# FPGA_GTX.net
KiCad netlist of a schematic drawn in Altium Designer
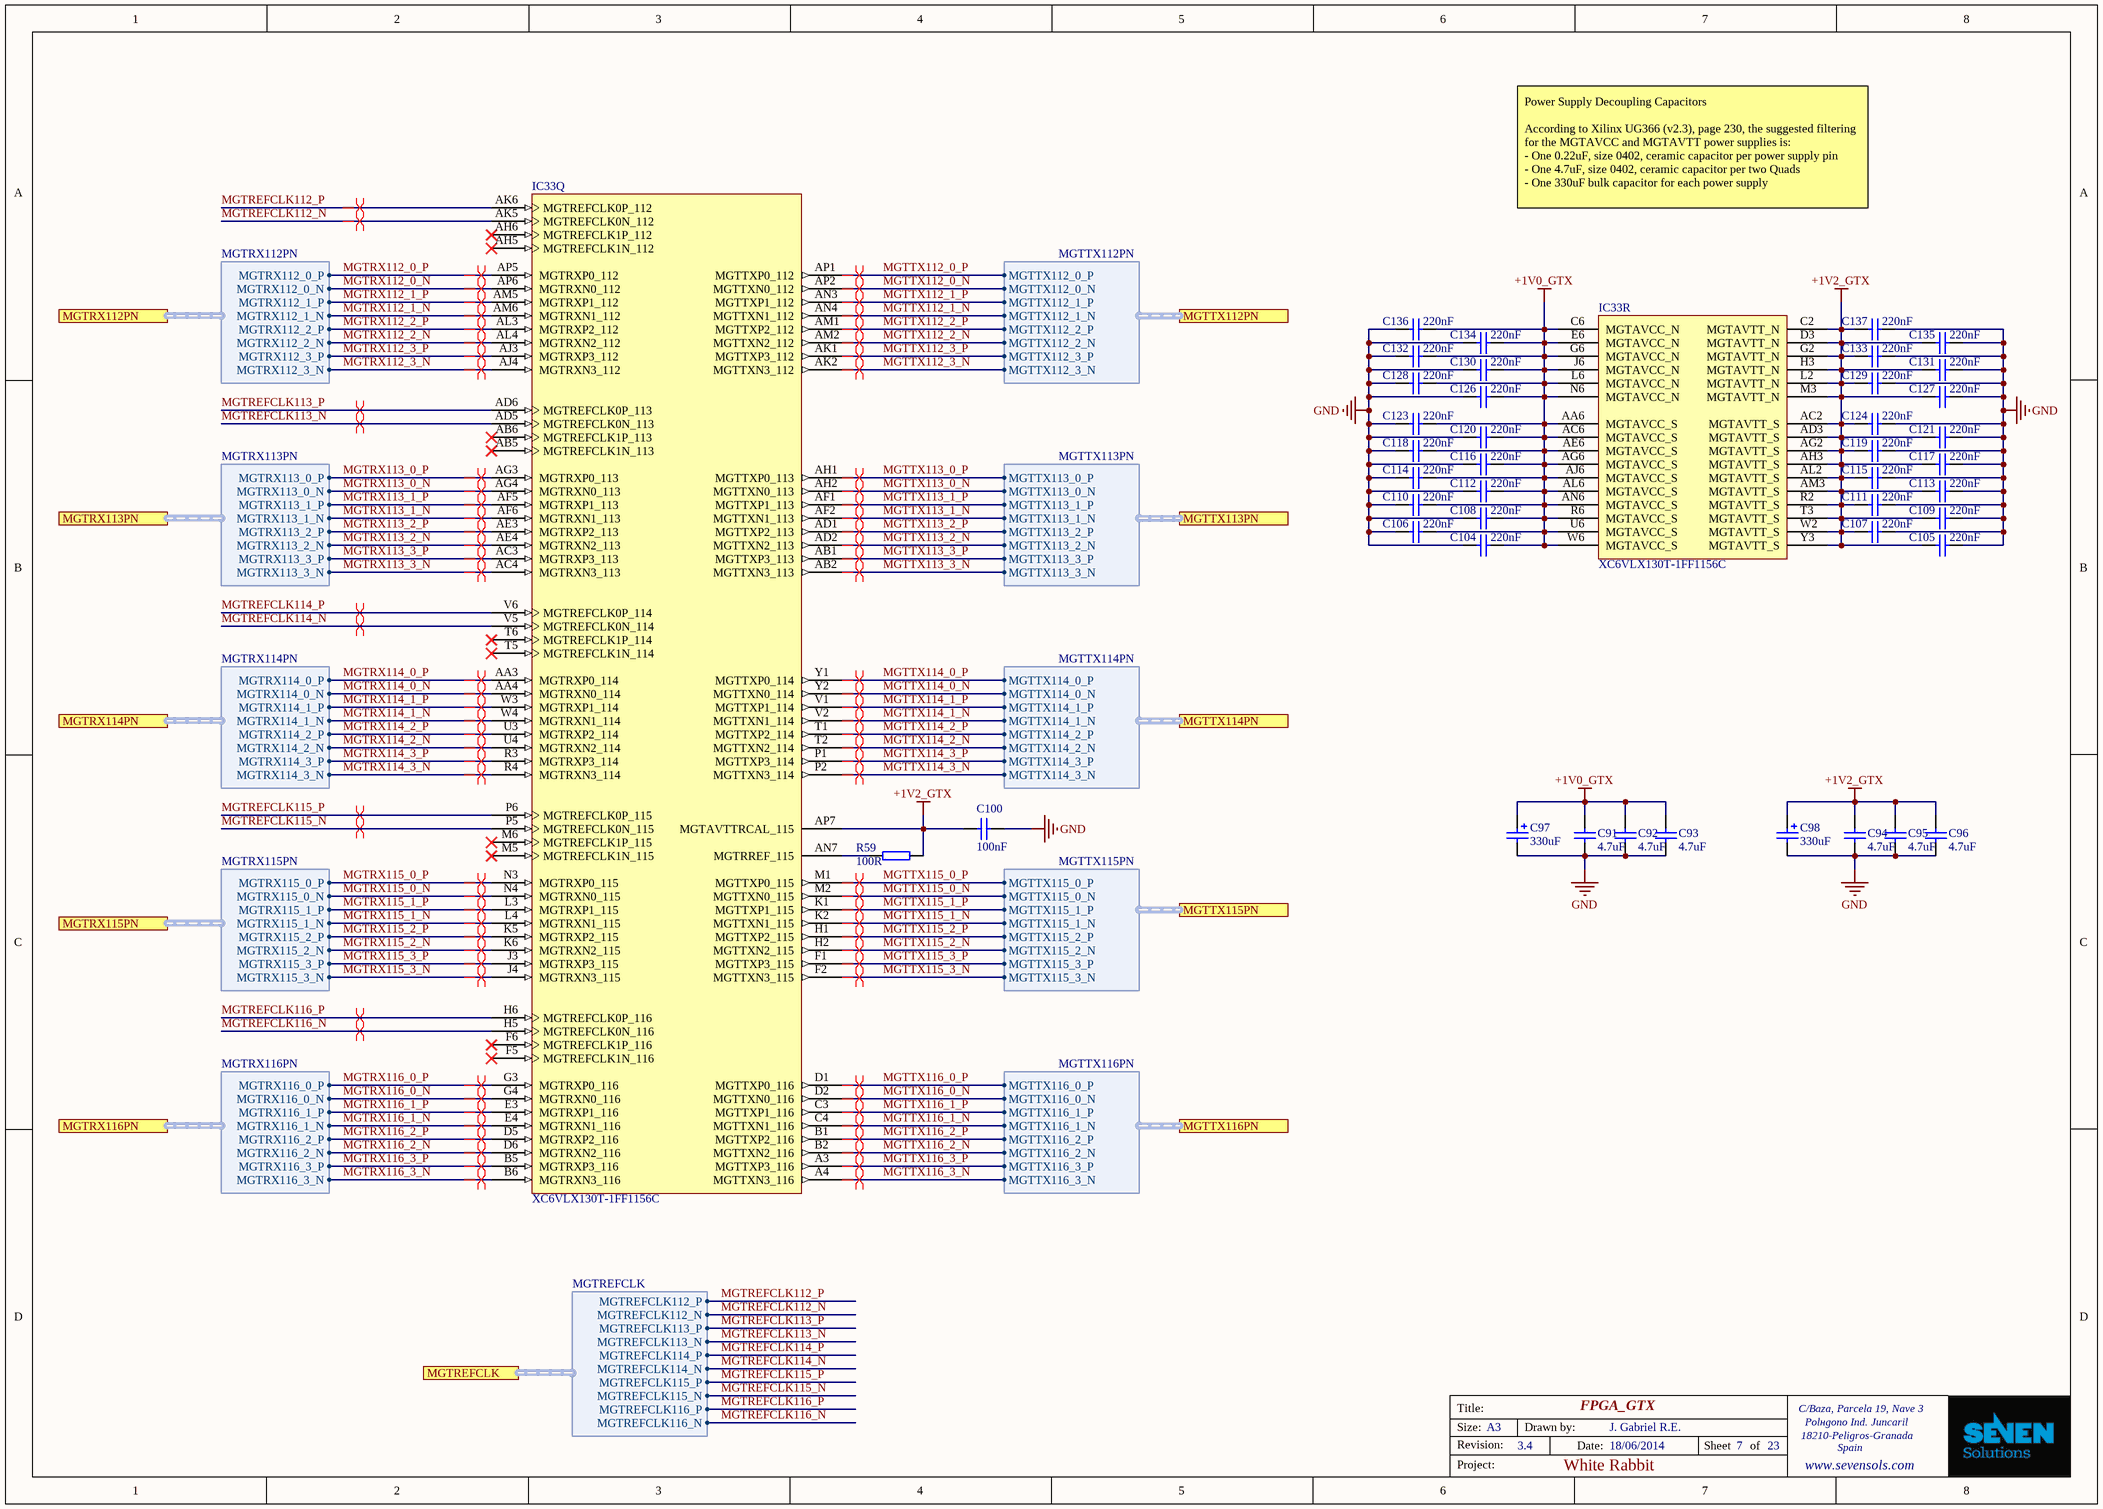
[diagram p0: FPGA_GTX.SchDoc]

(export (version "E")
  (design (tool "Eeschema 10.0.6"))
  (components
    (comp (ref "C91")
      (value "4.7uF")
      (footprint "CC1608-0603")
      (description "Capacitor")
      (fields
        (field (name "TOLERANCE") "±10%")
        (field (name "VOLTAGE") "10V")
        (field (name "PUBLISHER") "Altium Limited")
      )
      (libsource (lib "wr_switch") (part "Cap"))
    )
    (comp (ref "C92")
      (value "4.7uF")
      (footprint "CC1608-0603")
      (description "Capacitor")
      (fields
        (field (name "TOLERANCE") "±10%")
        (field (name "VOLTAGE") "10V")
        (field (name "PUBLISHER") "Altium Limited")
      )
      (libsource (lib "wr_switch") (part "Cap"))
    )
    (comp (ref "C93")
      (value "4.7uF")
      (footprint "CC1608-0603")
      (description "Capacitor")
      (fields
        (field (name "TOLERANCE") "±10%")
        (field (name "VOLTAGE") "10V")
        (field (name "PUBLISHER") "Altium Limited")
      )
      (libsource (lib "wr_switch") (part "Cap"))
    )
    (comp (ref "C94")
      (value "4.7uF")
      (footprint "CC1608-0603")
      (description "Capacitor")
      (fields
        (field (name "TOLERANCE") "±10%")
        (field (name "VOLTAGE") "10V")
        (field (name "PUBLISHER") "Altium Limited")
      )
      (libsource (lib "wr_switch") (part "Cap"))
    )
    (comp (ref "C95")
      (value "4.7uF")
      (footprint "CC1608-0603")
      (description "Capacitor")
      (fields
        (field (name "TOLERANCE") "±10%")
        (field (name "VOLTAGE") "10V")
        (field (name "PUBLISHER") "Altium Limited")
      )
      (libsource (lib "wr_switch") (part "Cap"))
    )
    (comp (ref "C96")
      (value "4.7uF")
      (footprint "CC1608-0603")
      (description "Capacitor")
      (fields
        (field (name "TOLERANCE") "±10%")
        (field (name "VOLTAGE") "10V")
        (field (name "PUBLISHER") "Altium Limited")
      )
      (libsource (lib "wr_switch") (part "Cap"))
    )
    (comp (ref "C97")
      (value "330uF")
      (footprint "D")
      (description "Polarized Capacitor Tantalum")
      (fields
        (field (name "TOLERANCE") "±20%")
        (field (name "VOLTAGE") "6.3V")
        (field (name "PUBLISHER") "Altium Limited")
      )
      (libsource (lib "wr_switch") (part "Cap Pol1"))
    )
    (comp (ref "C98")
      (value "330uF")
      (footprint "D")
      (description "Polarized Capacitor Tantalum")
      (fields
        (field (name "TOLERANCE") "±20%")
        (field (name "VOLTAGE") "6.3V")
        (field (name "PUBLISHER") "Altium Limited")
      )
      (libsource (lib "wr_switch") (part "Cap Pol1"))
    )
    (comp (ref "C100")
      (value "100nF")
      (footprint "CC1005-0402")
      (description "Capacitor")
      (fields
        (field (name "TOLERANCE") "±10%")
        (field (name "VOLTAGE") "16V")
        (field (name "PUBLISHER") "Altium Limited")
      )
      (libsource (lib "wr_switch") (part "Cap"))
    )
    (comp (ref "C104")
      (value "220nF")
      (footprint "CC1005-0402")
      (description "Capacitor")
      (fields
        (field (name "TOLERANCE") "±10%")
        (field (name "VOLTAGE") "16V")
        (field (name "PUBLISHER") "Altium Limited")
      )
      (libsource (lib "wr_switch") (part "Cap"))
    )
    (comp (ref "C105")
      (value "220nF")
      (footprint "CC1005-0402")
      (description "Capacitor")
      (fields
        (field (name "TOLERANCE") "±10%")
        (field (name "VOLTAGE") "16V")
        (field (name "PUBLISHER") "Altium Limited")
      )
      (libsource (lib "wr_switch") (part "Cap"))
    )
    (comp (ref "C106")
      (value "220nF")
      (footprint "CC1005-0402")
      (description "Capacitor")
      (fields
        (field (name "TOLERANCE") "±10%")
        (field (name "VOLTAGE") "16V")
        (field (name "PUBLISHER") "Altium Limited")
      )
      (libsource (lib "wr_switch") (part "Cap"))
    )
    (comp (ref "C107")
      (value "220nF")
      (footprint "CC1005-0402")
      (description "Capacitor")
      (fields
        (field (name "TOLERANCE") "±10%")
        (field (name "VOLTAGE") "16V")
        (field (name "PUBLISHER") "Altium Limited")
      )
      (libsource (lib "wr_switch") (part "Cap"))
    )
    (comp (ref "C108")
      (value "220nF")
      (footprint "CC1005-0402")
      (description "Capacitor")
      (fields
        (field (name "TOLERANCE") "±10%")
        (field (name "VOLTAGE") "16V")
        (field (name "PUBLISHER") "Altium Limited")
      )
      (libsource (lib "wr_switch") (part "Cap"))
    )
    (comp (ref "C109")
      (value "220nF")
      (footprint "CC1005-0402")
      (description "Capacitor")
      (fields
        (field (name "TOLERANCE") "±10%")
        (field (name "VOLTAGE") "16V")
        (field (name "PUBLISHER") "Altium Limited")
      )
      (libsource (lib "wr_switch") (part "Cap"))
    )
    (comp (ref "C110")
      (value "220nF")
      (footprint "CC1005-0402")
      (description "Capacitor")
      (fields
        (field (name "TOLERANCE") "±10%")
        (field (name "VOLTAGE") "16V")
        (field (name "PUBLISHER") "Altium Limited")
      )
      (libsource (lib "wr_switch") (part "Cap"))
    )
    (comp (ref "C111")
      (value "220nF")
      (footprint "CC1005-0402")
      (description "Capacitor")
      (fields
        (field (name "TOLERANCE") "±10%")
        (field (name "VOLTAGE") "16V")
        (field (name "PUBLISHER") "Altium Limited")
      )
      (libsource (lib "wr_switch") (part "Cap"))
    )
    (comp (ref "C112")
      (value "220nF")
      (footprint "CC1005-0402")
      (description "Capacitor")
      (fields
        (field (name "TOLERANCE") "±10%")
        (field (name "VOLTAGE") "16V")
        (field (name "PUBLISHER") "Altium Limited")
      )
      (libsource (lib "wr_switch") (part "Cap"))
    )
    (comp (ref "C113")
      (value "220nF")
      (footprint "CC1005-0402")
      (description "Capacitor")
      (fields
        (field (name "TOLERANCE") "±10%")
        (field (name "VOLTAGE") "16V")
        (field (name "PUBLISHER") "Altium Limited")
      )
      (libsource (lib "wr_switch") (part "Cap"))
    )
    (comp (ref "C114")
      (value "220nF")
      (footprint "CC1005-0402")
      (description "Capacitor")
      (fields
        (field (name "TOLERANCE") "±10%")
        (field (name "VOLTAGE") "16V")
        (field (name "PUBLISHER") "Altium Limited")
      )
      (libsource (lib "wr_switch") (part "Cap"))
    )
    (comp (ref "C115")
      (value "220nF")
      (footprint "CC1005-0402")
      (description "Capacitor")
      (fields
        (field (name "TOLERANCE") "±10%")
        (field (name "VOLTAGE") "16V")
        (field (name "PUBLISHER") "Altium Limited")
      )
      (libsource (lib "wr_switch") (part "Cap"))
    )
    (comp (ref "C116")
      (value "220nF")
      (footprint "CC1005-0402")
      (description "Capacitor")
      (fields
        (field (name "TOLERANCE") "±10%")
        (field (name "VOLTAGE") "16V")
        (field (name "PUBLISHER") "Altium Limited")
      )
      (libsource (lib "wr_switch") (part "Cap"))
    )
    (comp (ref "C117")
      (value "220nF")
      (footprint "CC1005-0402")
      (description "Capacitor")
      (fields
        (field (name "TOLERANCE") "±10%")
        (field (name "VOLTAGE") "16V")
        (field (name "PUBLISHER") "Altium Limited")
      )
      (libsource (lib "wr_switch") (part "Cap"))
    )
    (comp (ref "C118")
      (value "220nF")
      (footprint "CC1005-0402")
      (description "Capacitor")
      (fields
        (field (name "TOLERANCE") "±10%")
        (field (name "VOLTAGE") "16V")
        (field (name "PUBLISHER") "Altium Limited")
      )
      (libsource (lib "wr_switch") (part "Cap"))
    )
    (comp (ref "C119")
      (value "220nF")
      (footprint "CC1005-0402")
      (description "Capacitor")
      (fields
        (field (name "TOLERANCE") "±10%")
        (field (name "VOLTAGE") "16V")
        (field (name "PUBLISHER") "Altium Limited")
      )
      (libsource (lib "wr_switch") (part "Cap"))
    )
    (comp (ref "C120")
      (value "220nF")
      (footprint "CC1005-0402")
      (description "Capacitor")
      (fields
        (field (name "TOLERANCE") "±10%")
        (field (name "VOLTAGE") "16V")
        (field (name "PUBLISHER") "Altium Limited")
      )
      (libsource (lib "wr_switch") (part "Cap"))
    )
    (comp (ref "C121")
      (value "220nF")
      (footprint "CC1005-0402")
      (description "Capacitor")
      (fields
        (field (name "TOLERANCE") "±10%")
        (field (name "VOLTAGE") "16V")
        (field (name "PUBLISHER") "Altium Limited")
      )
      (libsource (lib "wr_switch") (part "Cap"))
    )
    (comp (ref "C123")
      (value "220nF")
      (footprint "CC1005-0402")
      (description "Capacitor")
      (fields
        (field (name "TOLERANCE") "±10%")
        (field (name "VOLTAGE") "16V")
        (field (name "PUBLISHER") "Altium Limited")
      )
      (libsource (lib "wr_switch") (part "Cap"))
    )
    (comp (ref "C124")
      (value "220nF")
      (footprint "CC1005-0402")
      (description "Capacitor")
      (fields
        (field (name "TOLERANCE") "±10%")
        (field (name "VOLTAGE") "16V")
        (field (name "PUBLISHER") "Altium Limited")
      )
      (libsource (lib "wr_switch") (part "Cap"))
    )
    (comp (ref "C126")
      (value "220nF")
      (footprint "CC1005-0402")
      (description "Capacitor")
      (fields
        (field (name "TOLERANCE") "±10%")
        (field (name "VOLTAGE") "16V")
        (field (name "PUBLISHER") "Altium Limited")
      )
      (libsource (lib "wr_switch") (part "Cap"))
    )
    (comp (ref "C127")
      (value "220nF")
      (footprint "CC1005-0402")
      (description "Capacitor")
      (fields
        (field (name "TOLERANCE") "±10%")
        (field (name "VOLTAGE") "16V")
        (field (name "PUBLISHER") "Altium Limited")
      )
      (libsource (lib "wr_switch") (part "Cap"))
    )
    (comp (ref "C128")
      (value "220nF")
      (footprint "CC1005-0402")
      (description "Capacitor")
      (fields
        (field (name "TOLERANCE") "±10%")
        (field (name "VOLTAGE") "16V")
        (field (name "PUBLISHER") "Altium Limited")
      )
      (libsource (lib "wr_switch") (part "Cap"))
    )
    (comp (ref "C129")
      (value "220nF")
      (footprint "CC1005-0402")
      (description "Capacitor")
      (fields
        (field (name "TOLERANCE") "±10%")
        (field (name "VOLTAGE") "16V")
        (field (name "PUBLISHER") "Altium Limited")
      )
      (libsource (lib "wr_switch") (part "Cap"))
    )
    (comp (ref "C130")
      (value "220nF")
      (footprint "CC1005-0402")
      (description "Capacitor")
      (fields
        (field (name "TOLERANCE") "±10%")
        (field (name "VOLTAGE") "16V")
        (field (name "PUBLISHER") "Altium Limited")
      )
      (libsource (lib "wr_switch") (part "Cap"))
    )
    (comp (ref "C131")
      (value "220nF")
      (footprint "CC1005-0402")
      (description "Capacitor")
      (fields
        (field (name "TOLERANCE") "±10%")
        (field (name "VOLTAGE") "16V")
        (field (name "PUBLISHER") "Altium Limited")
      )
      (libsource (lib "wr_switch") (part "Cap"))
    )
    (comp (ref "C132")
      (value "220nF")
      (footprint "CC1005-0402")
      (description "Capacitor")
      (fields
        (field (name "TOLERANCE") "±10%")
        (field (name "VOLTAGE") "16V")
        (field (name "PUBLISHER") "Altium Limited")
      )
      (libsource (lib "wr_switch") (part "Cap"))
    )
    (comp (ref "C133")
      (value "220nF")
      (footprint "CC1005-0402")
      (description "Capacitor")
      (fields
        (field (name "TOLERANCE") "±10%")
        (field (name "VOLTAGE") "16V")
        (field (name "PUBLISHER") "Altium Limited")
      )
      (libsource (lib "wr_switch") (part "Cap"))
    )
    (comp (ref "C134")
      (value "220nF")
      (footprint "CC1005-0402")
      (description "Capacitor")
      (fields
        (field (name "TOLERANCE") "±10%")
        (field (name "VOLTAGE") "16V")
        (field (name "PUBLISHER") "Altium Limited")
      )
      (libsource (lib "wr_switch") (part "Cap"))
    )
    (comp (ref "C135")
      (value "220nF")
      (footprint "CC1005-0402")
      (description "Capacitor")
      (fields
        (field (name "TOLERANCE") "±10%")
        (field (name "VOLTAGE") "16V")
        (field (name "PUBLISHER") "Altium Limited")
      )
      (libsource (lib "wr_switch") (part "Cap"))
    )
    (comp (ref "C136")
      (value "220nF")
      (footprint "CC1005-0402")
      (description "Capacitor")
      (fields
        (field (name "TOLERANCE") "±10%")
        (field (name "VOLTAGE") "16V")
        (field (name "PUBLISHER") "Altium Limited")
      )
      (libsource (lib "wr_switch") (part "Cap"))
    )
    (comp (ref "C137")
      (value "220nF")
      (footprint "CC1005-0402")
      (description "Capacitor")
      (fields
        (field (name "TOLERANCE") "±10%")
        (field (name "VOLTAGE") "16V")
        (field (name "PUBLISHER") "Altium Limited")
      )
      (libsource (lib "wr_switch") (part "Cap"))
    )
    (comp (ref "IC33")
      (value "XC6VLX130T-1FF1156C")
      (footprint "FF1156")
      (fields (field (name "PUBLISHER") "Altium Limited"))
      (libsource (lib "Xilinx Virtex-6") (part "XC6VLX130T-1FF1156C"))
    )
    (comp (ref "R59")
      (value "100R")
      (footprint "0402")
      (description "SMD Resistor")
      (fields (field (name "TOLERANCE") "±1%"))
      (libsource (lib "wr_switch") (part "RES_SMD"))
    )
  )
  (nets
    (net (code "12") (name "+1V0_GTX") (class "Default")
      (node (ref "C104") (pin "2") (pinfunction "2_2") (pintype "passive"))
      (node (ref "C106") (pin "2") (pinfunction "2_2") (pintype "passive"))
      (node (ref "C108") (pin "2") (pinfunction "2_2") (pintype "passive"))
      (node (ref "C110") (pin "2") (pinfunction "2_2") (pintype "passive"))
      (node (ref "C112") (pin "2") (pinfunction "2_2") (pintype "passive"))
      (node (ref "C114") (pin "2") (pinfunction "2_2") (pintype "passive"))
      (node (ref "C116") (pin "2") (pinfunction "2_2") (pintype "passive"))
      (node (ref "C118") (pin "2") (pinfunction "2_2") (pintype "passive"))
      (node (ref "C120") (pin "2") (pinfunction "2_2") (pintype "passive"))
      (node (ref "C123") (pin "2") (pinfunction "2_2") (pintype "passive"))
      (node (ref "C126") (pin "2") (pinfunction "2_2") (pintype "passive"))
      (node (ref "C128") (pin "2") (pinfunction "2_2") (pintype "passive"))
      (node (ref "C130") (pin "2") (pinfunction "2_2") (pintype "passive"))
      (node (ref "C132") (pin "2") (pinfunction "2_2") (pintype "passive"))
      (node (ref "C134") (pin "2") (pinfunction "2_2") (pintype "passive"))
      (node (ref "C136") (pin "2") (pinfunction "2_2") (pintype "passive"))
      (node (ref "C91") (pin "2") (pinfunction "2_2") (pintype "passive"))
      (node (ref "C92") (pin "2") (pinfunction "2_2") (pintype "passive"))
      (node (ref "C93") (pin "2") (pinfunction "2_2") (pintype "passive"))
      (node (ref "C97") (pin "1") (pinfunction "1_1") (pintype "passive"))
      (node (ref "IC33") (pin "AA6") (pinfunction "MGTAVCC_S_AA6") (pintype "power_in"))
      (node (ref "IC33") (pin "AC6") (pinfunction "MGTAVCC_S_AC6") (pintype "power_in"))
      (node (ref "IC33") (pin "AE6") (pinfunction "MGTAVCC_S_AE6") (pintype "power_in"))
      (node (ref "IC33") (pin "AG6") (pinfunction "MGTAVCC_S_AG6") (pintype "power_in"))
      (node (ref "IC33") (pin "AJ6") (pinfunction "MGTAVCC_S_AJ6") (pintype "power_in"))
      (node (ref "IC33") (pin "AL6") (pinfunction "MGTAVCC_S_AL6") (pintype "power_in"))
      (node (ref "IC33") (pin "AN6") (pinfunction "MGTAVCC_S_AN6") (pintype "power_in"))
      (node (ref "IC33") (pin "C6") (pinfunction "MGTAVCC_N_C6") (pintype "power_in"))
      (node (ref "IC33") (pin "E6") (pinfunction "MGTAVCC_N_E6") (pintype "power_in"))
      (node (ref "IC33") (pin "G6") (pinfunction "MGTAVCC_N_G6") (pintype "power_in"))
      (node (ref "IC33") (pin "J6") (pinfunction "MGTAVCC_N_J6") (pintype "power_in"))
      (node (ref "IC33") (pin "L6") (pinfunction "MGTAVCC_N_L6") (pintype "power_in"))
      (node (ref "IC33") (pin "N6") (pinfunction "MGTAVCC_N_N6") (pintype "power_in"))
      (node (ref "IC33") (pin "R6") (pinfunction "MGTAVCC_S_R6") (pintype "power_in"))
      (node (ref "IC33") (pin "U6") (pinfunction "MGTAVCC_S_U6") (pintype "power_in"))
      (node (ref "IC33") (pin "W6") (pinfunction "MGTAVCC_S_W6") (pintype "power_in"))
    )
    (net (code "13") (name "+1V2_GTX") (class "Default")
      (node (ref "C100") (pin "2") (pinfunction "2_2") (pintype "passive"))
      (node (ref "C105") (pin "1") (pinfunction "1_1") (pintype "passive"))
      (node (ref "C107") (pin "1") (pinfunction "1_1") (pintype "passive"))
      (node (ref "C109") (pin "1") (pinfunction "1_1") (pintype "passive"))
      (node (ref "C111") (pin "1") (pinfunction "1_1") (pintype "passive"))
      (node (ref "C113") (pin "1") (pinfunction "1_1") (pintype "passive"))
      (node (ref "C115") (pin "1") (pinfunction "1_1") (pintype "passive"))
      (node (ref "C117") (pin "1") (pinfunction "1_1") (pintype "passive"))
      (node (ref "C119") (pin "1") (pinfunction "1_1") (pintype "passive"))
      (node (ref "C121") (pin "1") (pinfunction "1_1") (pintype "passive"))
      (node (ref "C124") (pin "1") (pinfunction "1_1") (pintype "passive"))
      (node (ref "C127") (pin "1") (pinfunction "1_1") (pintype "passive"))
      (node (ref "C129") (pin "1") (pinfunction "1_1") (pintype "passive"))
      (node (ref "C131") (pin "1") (pinfunction "1_1") (pintype "passive"))
      (node (ref "C133") (pin "1") (pinfunction "1_1") (pintype "passive"))
      (node (ref "C135") (pin "1") (pinfunction "1_1") (pintype "passive"))
      (node (ref "C137") (pin "1") (pinfunction "1_1") (pintype "passive"))
      (node (ref "C94") (pin "2") (pinfunction "2_2") (pintype "passive"))
      (node (ref "C95") (pin "2") (pinfunction "2_2") (pintype "passive"))
      (node (ref "C96") (pin "2") (pinfunction "2_2") (pintype "passive"))
      (node (ref "C98") (pin "1") (pinfunction "1_1") (pintype "passive"))
      (node (ref "IC33") (pin "AC2") (pinfunction "MGTAVTT_S_AC2") (pintype "power_in"))
      (node (ref "IC33") (pin "AD3") (pinfunction "MGTAVTT_S_AD3") (pintype "power_in"))
      (node (ref "IC33") (pin "AG2") (pinfunction "MGTAVTT_S_AG2") (pintype "power_in"))
      (node (ref "IC33") (pin "AH3") (pinfunction "MGTAVTT_S_AH3") (pintype "power_in"))
      (node (ref "IC33") (pin "AL2") (pinfunction "MGTAVTT_S_AL2") (pintype "power_in"))
      (node (ref "IC33") (pin "AM3") (pinfunction "MGTAVTT_S_AM3") (pintype "power_in"))
      (node (ref "IC33") (pin "AP7") (pinfunction "MGTAVTTRCAL_115_AP7") (pintype "passive"))
      (node (ref "IC33") (pin "C2") (pinfunction "MGTAVTT_N_C2") (pintype "power_in"))
      (node (ref "IC33") (pin "D3") (pinfunction "MGTAVTT_N_D3") (pintype "power_in"))
      (node (ref "IC33") (pin "G2") (pinfunction "MGTAVTT_N_G2") (pintype "power_in"))
      (node (ref "IC33") (pin "H3") (pinfunction "MGTAVTT_N_H3") (pintype "power_in"))
      (node (ref "IC33") (pin "L2") (pinfunction "MGTAVTT_N_L2") (pintype "power_in"))
      (node (ref "IC33") (pin "M3") (pinfunction "MGTAVTT_N_M3") (pintype "power_in"))
      (node (ref "IC33") (pin "R2") (pinfunction "MGTAVTT_S_R2") (pintype "power_in"))
      (node (ref "IC33") (pin "T3") (pinfunction "MGTAVTT_S_T3") (pintype "power_in"))
      (node (ref "IC33") (pin "W2") (pinfunction "MGTAVTT_S_W2") (pintype "power_in"))
      (node (ref "IC33") (pin "Y3") (pinfunction "MGTAVTT_S_Y3") (pintype "power_in"))
      (node (ref "R59") (pin "1") (pinfunction "1_1") (pintype "passive"))
    )
    (net (code "14") (name "/MGTREFCLK112_N") (class "Default")
      (node (ref "IC33") (pin "AK5") (pinfunction "MGTREFCLK0N_112_AK5") (pintype "input"))
    )
    (net (code "15") (name "/MGTREFCLK112_P") (class "Default")
      (node (ref "IC33") (pin "AK6") (pinfunction "MGTREFCLK0P_112_AK6") (pintype "input"))
    )
    (net (code "16") (name "/MGTREFCLK113_N") (class "Default")
      (node (ref "IC33") (pin "AD5") (pinfunction "MGTREFCLK0N_113_AD5") (pintype "input"))
    )
    (net (code "17") (name "/MGTREFCLK113_P") (class "Default")
      (node (ref "IC33") (pin "AD6") (pinfunction "MGTREFCLK0P_113_AD6") (pintype "input"))
    )
    (net (code "18") (name "/MGTREFCLK114_N") (class "Default")
      (node (ref "IC33") (pin "V5") (pinfunction "MGTREFCLK0N_114_V5") (pintype "input"))
    )
    (net (code "19") (name "/MGTREFCLK114_P") (class "Default")
      (node (ref "IC33") (pin "V6") (pinfunction "MGTREFCLK0P_114_V6") (pintype "input"))
    )
    (net (code "20") (name "/MGTREFCLK115_N") (class "Default")
      (node (ref "IC33") (pin "P5") (pinfunction "MGTREFCLK0N_115_P5") (pintype "input"))
    )
    (net (code "21") (name "/MGTREFCLK115_P") (class "Default")
      (node (ref "IC33") (pin "P6") (pinfunction "MGTREFCLK0P_115_P6") (pintype "input"))
    )
    (net (code "22") (name "/MGTREFCLK116_N") (class "Default")
      (node (ref "IC33") (pin "H5") (pinfunction "MGTREFCLK0N_116_H5") (pintype "input"))
    )
    (net (code "23") (name "/MGTREFCLK116_P") (class "Default")
      (node (ref "IC33") (pin "H6") (pinfunction "MGTREFCLK0P_116_H6") (pintype "input"))
    )
    (net (code "24") (name "/MGTRX112_0_N") (class "Default")
      (node (ref "IC33") (pin "AP6") (pinfunction "MGTRXN0_112_AP6") (pintype "input"))
    )
    (net (code "25") (name "/MGTRX112_0_P") (class "Default")
      (node (ref "IC33") (pin "AP5") (pinfunction "MGTRXP0_112_AP5") (pintype "input"))
    )
    (net (code "26") (name "/MGTRX112_1_N") (class "Default")
      (node (ref "IC33") (pin "AM6") (pinfunction "MGTRXN1_112_AM6") (pintype "input"))
    )
    (net (code "27") (name "/MGTRX112_1_P") (class "Default")
      (node (ref "IC33") (pin "AM5") (pinfunction "MGTRXP1_112_AM5") (pintype "input"))
    )
    (net (code "28") (name "/MGTRX112_2_N") (class "Default")
      (node (ref "IC33") (pin "AL4") (pinfunction "MGTRXN2_112_AL4") (pintype "input"))
    )
    (net (code "29") (name "/MGTRX112_2_P") (class "Default")
      (node (ref "IC33") (pin "AL3") (pinfunction "MGTRXP2_112_AL3") (pintype "input"))
    )
    (net (code "30") (name "/MGTRX112_3_N") (class "Default")
      (node (ref "IC33") (pin "AJ4") (pinfunction "MGTRXN3_112_AJ4") (pintype "input"))
    )
    (net (code "31") (name "/MGTRX112_3_P") (class "Default")
      (node (ref "IC33") (pin "AJ3") (pinfunction "MGTRXP3_112_AJ3") (pintype "input"))
    )
    (net (code "32") (name "/MGTRX113_0_N") (class "Default")
      (node (ref "IC33") (pin "AG4") (pinfunction "MGTRXN0_113_AG4") (pintype "input"))
    )
    (net (code "33") (name "/MGTRX113_0_P") (class "Default")
      (node (ref "IC33") (pin "AG3") (pinfunction "MGTRXP0_113_AG3") (pintype "input"))
    )
    (net (code "34") (name "/MGTRX113_1_N") (class "Default")
      (node (ref "IC33") (pin "AF6") (pinfunction "MGTRXN1_113_AF6") (pintype "input"))
    )
    (net (code "35") (name "/MGTRX113_1_P") (class "Default")
      (node (ref "IC33") (pin "AF5") (pinfunction "MGTRXP1_113_AF5") (pintype "input"))
    )
    (net (code "36") (name "/MGTRX113_2_N") (class "Default")
      (node (ref "IC33") (pin "AE4") (pinfunction "MGTRXN2_113_AE4") (pintype "input"))
    )
    (net (code "37") (name "/MGTRX113_2_P") (class "Default")
      (node (ref "IC33") (pin "AE3") (pinfunction "MGTRXP2_113_AE3") (pintype "input"))
    )
    (net (code "38") (name "/MGTRX113_3_N") (class "Default")
      (node (ref "IC33") (pin "AC4") (pinfunction "MGTRXN3_113_AC4") (pintype "input"))
    )
    (net (code "39") (name "/MGTRX113_3_P") (class "Default")
      (node (ref "IC33") (pin "AC3") (pinfunction "MGTRXP3_113_AC3") (pintype "input"))
    )
    (net (code "40") (name "/MGTRX114_0_N") (class "Default")
      (node (ref "IC33") (pin "AA4") (pinfunction "MGTRXN0_114_AA4") (pintype "input"))
    )
    (net (code "41") (name "/MGTRX114_0_P") (class "Default")
      (node (ref "IC33") (pin "AA3") (pinfunction "MGTRXP0_114_AA3") (pintype "input"))
    )
    (net (code "42") (name "/MGTRX114_1_N") (class "Default")
      (node (ref "IC33") (pin "W4") (pinfunction "MGTRXN1_114_W4") (pintype "input"))
    )
    (net (code "43") (name "/MGTRX114_1_P") (class "Default")
      (node (ref "IC33") (pin "W3") (pinfunction "MGTRXP1_114_W3") (pintype "input"))
    )
    (net (code "44") (name "/MGTRX114_2_N") (class "Default")
      (node (ref "IC33") (pin "U4") (pinfunction "MGTRXN2_114_U4") (pintype "input"))
    )
    (net (code "45") (name "/MGTRX114_2_P") (class "Default")
      (node (ref "IC33") (pin "U3") (pinfunction "MGTRXP2_114_U3") (pintype "input"))
    )
    (net (code "46") (name "/MGTRX114_3_N") (class "Default")
      (node (ref "IC33") (pin "R4") (pinfunction "MGTRXN3_114_R4") (pintype "input"))
    )
    (net (code "47") (name "/MGTRX114_3_P") (class "Default")
      (node (ref "IC33") (pin "R3") (pinfunction "MGTRXP3_114_R3") (pintype "input"))
    )
    (net (code "48") (name "/MGTRX115_0_N") (class "Default")
      (node (ref "IC33") (pin "N4") (pinfunction "MGTRXN0_115_N4") (pintype "input"))
    )
    (net (code "49") (name "/MGTRX115_0_P") (class "Default")
      (node (ref "IC33") (pin "N3") (pinfunction "MGTRXP0_115_N3") (pintype "input"))
    )
    (net (code "50") (name "/MGTRX115_1_N") (class "Default")
      (node (ref "IC33") (pin "L4") (pinfunction "MGTRXN1_115_L4") (pintype "input"))
    )
    (net (code "51") (name "/MGTRX115_1_P") (class "Default")
      (node (ref "IC33") (pin "L3") (pinfunction "MGTRXP1_115_L3") (pintype "input"))
    )
    (net (code "52") (name "/MGTRX115_2_N") (class "Default")
      (node (ref "IC33") (pin "K6") (pinfunction "MGTRXN2_115_K6") (pintype "input"))
    )
    (net (code "53") (name "/MGTRX115_2_P") (class "Default")
      (node (ref "IC33") (pin "K5") (pinfunction "MGTRXP2_115_K5") (pintype "input"))
    )
    (net (code "54") (name "/MGTRX115_3_N") (class "Default")
      (node (ref "IC33") (pin "J4") (pinfunction "MGTRXN3_115_J4") (pintype "input"))
    )
    (net (code "55") (name "/MGTRX115_3_P") (class "Default")
      (node (ref "IC33") (pin "J3") (pinfunction "MGTRXP3_115_J3") (pintype "input"))
    )
    (net (code "56") (name "/MGTRX116_0_N") (class "Default")
      (node (ref "IC33") (pin "G4") (pinfunction "MGTRXN0_116_G4") (pintype "input"))
    )
    (net (code "57") (name "/MGTRX116_0_P") (class "Default")
      (node (ref "IC33") (pin "G3") (pinfunction "MGTRXP0_116_G3") (pintype "input"))
    )
    (net (code "58") (name "/MGTRX116_1_N") (class "Default")
      (node (ref "IC33") (pin "E4") (pinfunction "MGTRXN1_116_E4") (pintype "input"))
    )
    (net (code "59") (name "/MGTRX116_1_P") (class "Default")
      (node (ref "IC33") (pin "E3") (pinfunction "MGTRXP1_116_E3") (pintype "input"))
    )
    (net (code "60") (name "/MGTRX116_2_N") (class "Default")
      (node (ref "IC33") (pin "D6") (pinfunction "MGTRXN2_116_D6") (pintype "input"))
    )
    (net (code "61") (name "/MGTRX116_2_P") (class "Default")
      (node (ref "IC33") (pin "D5") (pinfunction "MGTRXP2_116_D5") (pintype "input"))
    )
    (net (code "62") (name "/MGTRX116_3_N") (class "Default")
      (node (ref "IC33") (pin "B6") (pinfunction "MGTRXN3_116_B6") (pintype "input"))
    )
    (net (code "63") (name "/MGTRX116_3_P") (class "Default")
      (node (ref "IC33") (pin "B5") (pinfunction "MGTRXP3_116_B5") (pintype "input"))
    )
    (net (code "64") (name "/MGTTX112_0_N") (class "Default")
      (node (ref "IC33") (pin "AP2") (pinfunction "MGTTXN0_112_AP2") (pintype "output"))
    )
    (net (code "65") (name "/MGTTX112_0_P") (class "Default")
      (node (ref "IC33") (pin "AP1") (pinfunction "MGTTXP0_112_AP1") (pintype "output"))
    )
    (net (code "66") (name "/MGTTX112_1_N") (class "Default")
      (node (ref "IC33") (pin "AN4") (pinfunction "MGTTXN1_112_AN4") (pintype "output"))
    )
    (net (code "67") (name "/MGTTX112_1_P") (class "Default")
      (node (ref "IC33") (pin "AN3") (pinfunction "MGTTXP1_112_AN3") (pintype "output"))
    )
    (net (code "68") (name "/MGTTX112_2_N") (class "Default")
      (node (ref "IC33") (pin "AM2") (pinfunction "MGTTXN2_112_AM2") (pintype "output"))
    )
    (net (code "69") (name "/MGTTX112_2_P") (class "Default")
      (node (ref "IC33") (pin "AM1") (pinfunction "MGTTXP2_112_AM1") (pintype "output"))
    )
    (net (code "70") (name "/MGTTX112_3_N") (class "Default")
      (node (ref "IC33") (pin "AK2") (pinfunction "MGTTXN3_112_AK2") (pintype "output"))
    )
    (net (code "71") (name "/MGTTX112_3_P") (class "Default")
      (node (ref "IC33") (pin "AK1") (pinfunction "MGTTXP3_112_AK1") (pintype "output"))
    )
    (net (code "72") (name "/MGTTX113_0_N") (class "Default")
      (node (ref "IC33") (pin "AH2") (pinfunction "MGTTXN0_113_AH2") (pintype "output"))
    )
    (net (code "73") (name "/MGTTX113_0_P") (class "Default")
      (node (ref "IC33") (pin "AH1") (pinfunction "MGTTXP0_113_AH1") (pintype "output"))
    )
    (net (code "74") (name "/MGTTX113_1_N") (class "Default")
      (node (ref "IC33") (pin "AF2") (pinfunction "MGTTXN1_113_AF2") (pintype "output"))
    )
    (net (code "75") (name "/MGTTX113_1_P") (class "Default")
      (node (ref "IC33") (pin "AF1") (pinfunction "MGTTXP1_113_AF1") (pintype "output"))
    )
    (net (code "76") (name "/MGTTX113_2_N") (class "Default")
      (node (ref "IC33") (pin "AD2") (pinfunction "MGTTXN2_113_AD2") (pintype "output"))
    )
    (net (code "77") (name "/MGTTX113_2_P") (class "Default")
      (node (ref "IC33") (pin "AD1") (pinfunction "MGTTXP2_113_AD1") (pintype "output"))
    )
    (net (code "78") (name "/MGTTX113_3_N") (class "Default")
      (node (ref "IC33") (pin "AB2") (pinfunction "MGTTXN3_113_AB2") (pintype "output"))
    )
    (net (code "79") (name "/MGTTX113_3_P") (class "Default")
      (node (ref "IC33") (pin "AB1") (pinfunction "MGTTXP3_113_AB1") (pintype "output"))
    )
    (net (code "80") (name "/MGTTX114_0_N") (class "Default")
      (node (ref "IC33") (pin "Y2") (pinfunction "MGTTXN0_114_Y2") (pintype "output"))
    )
    (net (code "81") (name "/MGTTX114_0_P") (class "Default")
      (node (ref "IC33") (pin "Y1") (pinfunction "MGTTXP0_114_Y1") (pintype "output"))
    )
    (net (code "82") (name "/MGTTX114_1_N") (class "Default")
      (node (ref "IC33") (pin "V2") (pinfunction "MGTTXN1_114_V2") (pintype "output"))
    )
    (net (code "83") (name "/MGTTX114_1_P") (class "Default")
      (node (ref "IC33") (pin "V1") (pinfunction "MGTTXP1_114_V1") (pintype "output"))
    )
    (net (code "84") (name "/MGTTX114_2_N") (class "Default")
      (node (ref "IC33") (pin "T2") (pinfunction "MGTTXN2_114_T2") (pintype "output"))
    )
    (net (code "85") (name "/MGTTX114_2_P") (class "Default")
      (node (ref "IC33") (pin "T1") (pinfunction "MGTTXP2_114_T1") (pintype "output"))
    )
    (net (code "86") (name "/MGTTX114_3_N") (class "Default")
      (node (ref "IC33") (pin "P2") (pinfunction "MGTTXN3_114_P2") (pintype "output"))
    )
    (net (code "87") (name "/MGTTX114_3_P") (class "Default")
      (node (ref "IC33") (pin "P1") (pinfunction "MGTTXP3_114_P1") (pintype "output"))
    )
    (net (code "88") (name "/MGTTX115_0_N") (class "Default")
      (node (ref "IC33") (pin "M2") (pinfunction "MGTTXN0_115_M2") (pintype "output"))
    )
    (net (code "89") (name "/MGTTX115_0_P") (class "Default")
      (node (ref "IC33") (pin "M1") (pinfunction "MGTTXP0_115_M1") (pintype "output"))
    )
    (net (code "90") (name "/MGTTX115_1_N") (class "Default")
      (node (ref "IC33") (pin "K2") (pinfunction "MGTTXN1_115_K2") (pintype "output"))
    )
    (net (code "91") (name "/MGTTX115_1_P") (class "Default")
      (node (ref "IC33") (pin "K1") (pinfunction "MGTTXP1_115_K1") (pintype "output"))
    )
    (net (code "92") (name "/MGTTX115_2_N") (class "Default")
      (node (ref "IC33") (pin "H2") (pinfunction "MGTTXN2_115_H2") (pintype "output"))
    )
    (net (code "93") (name "/MGTTX115_2_P") (class "Default")
      (node (ref "IC33") (pin "H1") (pinfunction "MGTTXP2_115_H1") (pintype "output"))
    )
    (net (code "94") (name "/MGTTX115_3_N") (class "Default")
      (node (ref "IC33") (pin "F2") (pinfunction "MGTTXN3_115_F2") (pintype "output"))
    )
    (net (code "95") (name "/MGTTX115_3_P") (class "Default")
      (node (ref "IC33") (pin "F1") (pinfunction "MGTTXP3_115_F1") (pintype "output"))
    )
    (net (code "96") (name "/MGTTX116_0_N") (class "Default")
      (node (ref "IC33") (pin "D2") (pinfunction "MGTTXN0_116_D2") (pintype "output"))
    )
    (net (code "97") (name "/MGTTX116_0_P") (class "Default")
      (node (ref "IC33") (pin "D1") (pinfunction "MGTTXP0_116_D1") (pintype "output"))
    )
    (net (code "98") (name "/MGTTX116_1_N") (class "Default")
      (node (ref "IC33") (pin "C4") (pinfunction "MGTTXN1_116_C4") (pintype "output"))
    )
    (net (code "99") (name "/MGTTX116_1_P") (class "Default")
      (node (ref "IC33") (pin "C3") (pinfunction "MGTTXP1_116_C3") (pintype "output"))
    )
    (net (code "100") (name "/MGTTX116_2_N") (class "Default")
      (node (ref "IC33") (pin "B2") (pinfunction "MGTTXN2_116_B2") (pintype "output"))
    )
    (net (code "101") (name "/MGTTX116_2_P") (class "Default")
      (node (ref "IC33") (pin "B1") (pinfunction "MGTTXP2_116_B1") (pintype "output"))
    )
    (net (code "102") (name "/MGTTX116_3_N") (class "Default")
      (node (ref "IC33") (pin "A4") (pinfunction "MGTTXN3_116_A4") (pintype "output"))
    )
    (net (code "103") (name "/MGTTX116_3_P") (class "Default")
      (node (ref "IC33") (pin "A3") (pinfunction "MGTTXP3_116_A3") (pintype "output"))
    )
    (net (code "115") (name "GND") (class "Default")
      (node (ref "C100") (pin "1") (pinfunction "1_1") (pintype "passive"))
      (node (ref "C104") (pin "1") (pinfunction "1_1") (pintype "passive"))
      (node (ref "C105") (pin "2") (pinfunction "2_2") (pintype "passive"))
      (node (ref "C106") (pin "1") (pinfunction "1_1") (pintype "passive"))
      (node (ref "C107") (pin "2") (pinfunction "2_2") (pintype "passive"))
      (node (ref "C108") (pin "1") (pinfunction "1_1") (pintype "passive"))
      (node (ref "C109") (pin "2") (pinfunction "2_2") (pintype "passive"))
      (node (ref "C110") (pin "1") (pinfunction "1_1") (pintype "passive"))
      (node (ref "C111") (pin "2") (pinfunction "2_2") (pintype "passive"))
      (node (ref "C112") (pin "1") (pinfunction "1_1") (pintype "passive"))
      (node (ref "C113") (pin "2") (pinfunction "2_2") (pintype "passive"))
      (node (ref "C114") (pin "1") (pinfunction "1_1") (pintype "passive"))
      (node (ref "C115") (pin "2") (pinfunction "2_2") (pintype "passive"))
      (node (ref "C116") (pin "1") (pinfunction "1_1") (pintype "passive"))
      (node (ref "C117") (pin "2") (pinfunction "2_2") (pintype "passive"))
      (node (ref "C118") (pin "1") (pinfunction "1_1") (pintype "passive"))
      (node (ref "C119") (pin "2") (pinfunction "2_2") (pintype "passive"))
      (node (ref "C120") (pin "1") (pinfunction "1_1") (pintype "passive"))
      (node (ref "C121") (pin "2") (pinfunction "2_2") (pintype "passive"))
      (node (ref "C123") (pin "1") (pinfunction "1_1") (pintype "passive"))
      (node (ref "C124") (pin "2") (pinfunction "2_2") (pintype "passive"))
      (node (ref "C126") (pin "1") (pinfunction "1_1") (pintype "passive"))
      (node (ref "C127") (pin "2") (pinfunction "2_2") (pintype "passive"))
      (node (ref "C128") (pin "1") (pinfunction "1_1") (pintype "passive"))
      (node (ref "C129") (pin "2") (pinfunction "2_2") (pintype "passive"))
      (node (ref "C130") (pin "1") (pinfunction "1_1") (pintype "passive"))
      (node (ref "C131") (pin "2") (pinfunction "2_2") (pintype "passive"))
      (node (ref "C132") (pin "1") (pinfunction "1_1") (pintype "passive"))
      (node (ref "C133") (pin "2") (pinfunction "2_2") (pintype "passive"))
      (node (ref "C134") (pin "1") (pinfunction "1_1") (pintype "passive"))
      (node (ref "C135") (pin "2") (pinfunction "2_2") (pintype "passive"))
      (node (ref "C136") (pin "1") (pinfunction "1_1") (pintype "passive"))
      (node (ref "C137") (pin "2") (pinfunction "2_2") (pintype "passive"))
      (node (ref "C91") (pin "1") (pinfunction "1_1") (pintype "passive"))
      (node (ref "C92") (pin "1") (pinfunction "1_1") (pintype "passive"))
      (node (ref "C93") (pin "1") (pinfunction "1_1") (pintype "passive"))
      (node (ref "C94") (pin "1") (pinfunction "1_1") (pintype "passive"))
      (node (ref "C95") (pin "1") (pinfunction "1_1") (pintype "passive"))
      (node (ref "C96") (pin "1") (pinfunction "1_1") (pintype "passive"))
      (node (ref "C97") (pin "2") (pinfunction "2_2") (pintype "passive"))
      (node (ref "C98") (pin "2") (pinfunction "2_2") (pintype "passive"))
    )
    (net (code "116") (name "Net-(IC33Q-MGTRREF_115)") (class "Default")
      (node (ref "IC33") (pin "AN7") (pinfunction "MGTRREF_115_AN7") (pintype "passive"))
      (node (ref "R59") (pin "2") (pinfunction "2_2") (pintype "passive"))
    )
    (net (code "117") (name "unconnected-(IC33Q-MGTREFCLK1N_112-PadAH5)") (class "Default")
      (node (ref "IC33") (pin "AH5") (pinfunction "MGTREFCLK1N_112_AH5") (pintype "input+no_connect"))
    )
    (net (code "118") (name "unconnected-(IC33Q-MGTREFCLK1N_113-PadAB5)") (class "Default")
      (node (ref "IC33") (pin "AB5") (pinfunction "MGTREFCLK1N_113_AB5") (pintype "input+no_connect"))
    )
    (net (code "119") (name "unconnected-(IC33Q-MGTREFCLK1N_114-PadT5)") (class "Default")
      (node (ref "IC33") (pin "T5") (pinfunction "MGTREFCLK1N_114_T5") (pintype "input+no_connect"))
    )
    (net (code "120") (name "unconnected-(IC33Q-MGTREFCLK1N_115-PadM5)") (class "Default")
      (node (ref "IC33") (pin "M5") (pinfunction "MGTREFCLK1N_115_M5") (pintype "input+no_connect"))
    )
    (net (code "121") (name "unconnected-(IC33Q-MGTREFCLK1N_116-PadF5)") (class "Default")
      (node (ref "IC33") (pin "F5") (pinfunction "MGTREFCLK1N_116_F5") (pintype "input+no_connect"))
    )
    (net (code "122") (name "unconnected-(IC33Q-MGTREFCLK1P_112-PadAH6)") (class "Default")
      (node (ref "IC33") (pin "AH6") (pinfunction "MGTREFCLK1P_112_AH6") (pintype "input+no_connect"))
    )
    (net (code "123") (name "unconnected-(IC33Q-MGTREFCLK1P_113-PadAB6)") (class "Default")
      (node (ref "IC33") (pin "AB6") (pinfunction "MGTREFCLK1P_113_AB6") (pintype "input+no_connect"))
    )
    (net (code "124") (name "unconnected-(IC33Q-MGTREFCLK1P_114-PadT6)") (class "Default")
      (node (ref "IC33") (pin "T6") (pinfunction "MGTREFCLK1P_114_T6") (pintype "input+no_connect"))
    )
    (net (code "125") (name "unconnected-(IC33Q-MGTREFCLK1P_115-PadM6)") (class "Default")
      (node (ref "IC33") (pin "M6") (pinfunction "MGTREFCLK1P_115_M6") (pintype "input+no_connect"))
    )
    (net (code "126") (name "unconnected-(IC33Q-MGTREFCLK1P_116-PadF6)") (class "Default")
      (node (ref "IC33") (pin "F6") (pinfunction "MGTREFCLK1P_116_F6") (pintype "input+no_connect"))
    )
  )
)
